# M113C.net
KiCad netlist of a schematic drawn in EAGLE
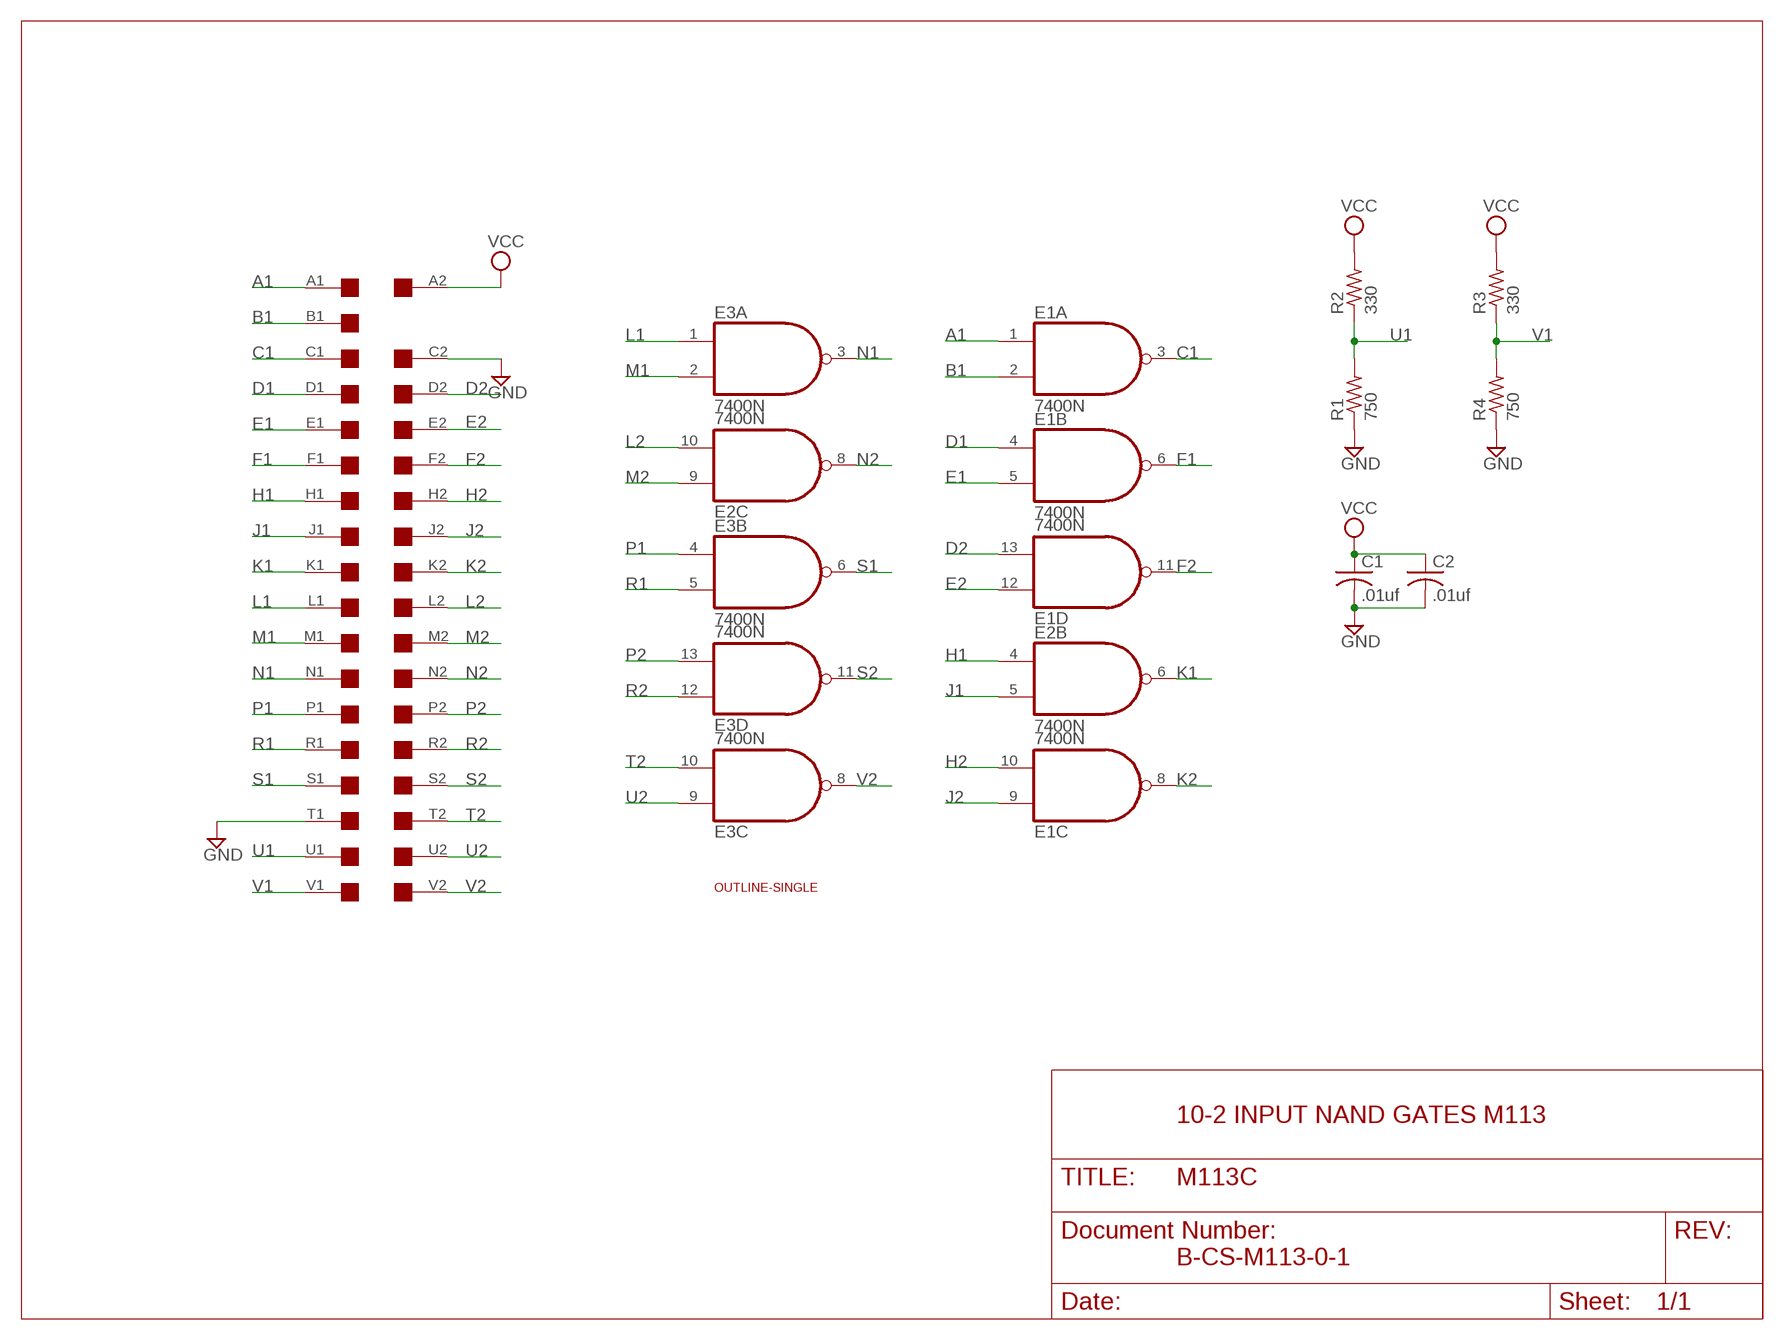
[diagram p0: schematic, sheet 1]

(export (version "E")
  (design (tool "Eeschema 10.0.6"))
  (components
    (comp (ref "C1")
      (value ".01uf")
      (footprint "eagle-import:C050-025X075")
      (libsource (lib "eagle-import") (part "C-US050-025X075"))
    )
    (comp (ref "C2")
      (value ".01uf")
      (footprint "eagle-import:C050-025X075")
      (libsource (lib "eagle-import") (part "C-US050-025X075"))
    )
    (comp (ref "E1")
      (value "7400N")
      (footprint "eagle-import:DIL14")
      (libsource (lib "eagle-import") (part "7400N"))
    )
    (comp (ref "E2")
      (value "7400N")
      (footprint "eagle-import:DIL14")
      (libsource (lib "eagle-import") (part "7400N"))
    )
    (comp (ref "E3")
      (value "7400N")
      (footprint "eagle-import:DIL14")
      (libsource (lib "eagle-import") (part "7400N"))
    )
    (comp (ref "R1")
      (value "750")
      (footprint "eagle-import:0207_10")
      (libsource (lib "eagle-import") (part "R-US_0207/10"))
    )
    (comp (ref "R2")
      (value "330")
      (footprint "eagle-import:0207_10")
      (libsource (lib "eagle-import") (part "R-US_0207/10"))
    )
    (comp (ref "R3")
      (value "330")
      (footprint "eagle-import:0207_10")
      (libsource (lib "eagle-import") (part "R-US_0207/10"))
    )
    (comp (ref "R4")
      (value "750")
      (footprint "eagle-import:0207_10")
      (libsource (lib "eagle-import") (part "R-US_0207/10"))
    )
    (comp (ref "U$1")
      (value "SINGLE")
      (footprint "eagle-import:EDGE-CON2")
      (libsource (lib "eagle-import") (part "SINGLE"))
    )
    (comp (ref "U$2")
      (value "OUTLINE-SINGLE")
      (footprint "eagle-import:SINGLE")
      (libsource (lib "eagle-import") (part "OUTLINE-SINGLE"))
    )
  )
  (nets
    (net (code "1") (name "/A1") (class "Default")
      (node (ref "E1") (pin "1") (pinfunction "I0_1") (pintype "input"))
      (node (ref "U$1") (pin "A1") (pinfunction "1_A1") (pintype "bidirectional"))
    )
    (net (code "2") (name "/B1") (class "Default")
      (node (ref "E1") (pin "2") (pinfunction "I1_2") (pintype "input"))
      (node (ref "U$1") (pin "B1") (pinfunction "1_B1") (pintype "bidirectional"))
    )
    (net (code "3") (name "/C1") (class "Default")
      (node (ref "E1") (pin "3") (pinfunction "O_3") (pintype "output"))
      (node (ref "U$1") (pin "C1") (pinfunction "1_C1") (pintype "bidirectional"))
    )
    (net (code "4") (name "/D1") (class "Default")
      (node (ref "E1") (pin "4") (pinfunction "I0_4") (pintype "input"))
      (node (ref "U$1") (pin "D1") (pinfunction "1_D1") (pintype "bidirectional"))
    )
    (net (code "5") (name "/D2") (class "Default")
      (node (ref "E1") (pin "13") (pinfunction "I1_13") (pintype "input"))
      (node (ref "U$1") (pin "D2") (pinfunction "1_D2") (pintype "bidirectional"))
    )
    (net (code "6") (name "/E1") (class "Default")
      (node (ref "E1") (pin "5") (pinfunction "I1_5") (pintype "input"))
      (node (ref "U$1") (pin "E1") (pinfunction "1_E1") (pintype "bidirectional"))
    )
    (net (code "7") (name "/E2") (class "Default")
      (node (ref "E1") (pin "12") (pinfunction "I0_12") (pintype "input"))
      (node (ref "U$1") (pin "E2") (pinfunction "1_E2") (pintype "bidirectional"))
    )
    (net (code "8") (name "/F1") (class "Default")
      (node (ref "E1") (pin "6") (pinfunction "O_6") (pintype "output"))
      (node (ref "U$1") (pin "F1") (pinfunction "1_F1") (pintype "bidirectional"))
    )
    (net (code "9") (name "/F2") (class "Default")
      (node (ref "E1") (pin "11") (pinfunction "O_11") (pintype "output"))
      (node (ref "U$1") (pin "F2") (pinfunction "1_F2") (pintype "bidirectional"))
    )
    (net (code "10") (name "/H1") (class "Default")
      (node (ref "E2") (pin "4") (pinfunction "I0_4") (pintype "input"))
      (node (ref "U$1") (pin "H1") (pinfunction "1_H1") (pintype "bidirectional"))
    )
    (net (code "11") (name "/H2") (class "Default")
      (node (ref "E1") (pin "10") (pinfunction "I1_10") (pintype "input"))
      (node (ref "U$1") (pin "H2") (pinfunction "1_H2") (pintype "bidirectional"))
    )
    (net (code "12") (name "/J1") (class "Default")
      (node (ref "E2") (pin "5") (pinfunction "I1_5") (pintype "input"))
      (node (ref "U$1") (pin "J1") (pinfunction "1_J1") (pintype "bidirectional"))
    )
    (net (code "13") (name "/J2") (class "Default")
      (node (ref "E1") (pin "9") (pinfunction "I0_9") (pintype "input"))
      (node (ref "U$1") (pin "J2") (pinfunction "1_J2") (pintype "bidirectional"))
    )
    (net (code "14") (name "/K1") (class "Default")
      (node (ref "E2") (pin "6") (pinfunction "O_6") (pintype "output"))
      (node (ref "U$1") (pin "K1") (pinfunction "1_K1") (pintype "bidirectional"))
    )
    (net (code "15") (name "/K2") (class "Default")
      (node (ref "E1") (pin "8") (pinfunction "O_8") (pintype "output"))
      (node (ref "U$1") (pin "K2") (pinfunction "1_K2") (pintype "bidirectional"))
    )
    (net (code "16") (name "/L1") (class "Default")
      (node (ref "E3") (pin "1") (pinfunction "I0_1") (pintype "input"))
      (node (ref "U$1") (pin "L1") (pinfunction "1_L1") (pintype "bidirectional"))
    )
    (net (code "17") (name "/L2") (class "Default")
      (node (ref "E2") (pin "10") (pinfunction "I1_10") (pintype "input"))
      (node (ref "U$1") (pin "L2") (pinfunction "1_L2") (pintype "bidirectional"))
    )
    (net (code "18") (name "/M1") (class "Default")
      (node (ref "E3") (pin "2") (pinfunction "I1_2") (pintype "input"))
      (node (ref "U$1") (pin "M1") (pinfunction "1_M1") (pintype "bidirectional"))
    )
    (net (code "19") (name "/M2") (class "Default")
      (node (ref "E2") (pin "9") (pinfunction "I0_9") (pintype "input"))
      (node (ref "U$1") (pin "M2") (pinfunction "1_M2") (pintype "bidirectional"))
    )
    (net (code "20") (name "/N1") (class "Default")
      (node (ref "E3") (pin "3") (pinfunction "O_3") (pintype "output"))
      (node (ref "U$1") (pin "N1") (pinfunction "1_N1") (pintype "bidirectional"))
    )
    (net (code "21") (name "/N2") (class "Default")
      (node (ref "E2") (pin "8") (pinfunction "O_8") (pintype "output"))
      (node (ref "U$1") (pin "N2") (pinfunction "1_N2") (pintype "bidirectional"))
    )
    (net (code "22") (name "/P1") (class "Default")
      (node (ref "E3") (pin "4") (pinfunction "I0_4") (pintype "input"))
      (node (ref "U$1") (pin "P1") (pinfunction "1_P1") (pintype "bidirectional"))
    )
    (net (code "23") (name "/P2") (class "Default")
      (node (ref "E3") (pin "13") (pinfunction "I1_13") (pintype "input"))
      (node (ref "U$1") (pin "P2") (pinfunction "1_P2") (pintype "bidirectional"))
    )
    (net (code "24") (name "/R1") (class "Default")
      (node (ref "E3") (pin "5") (pinfunction "I1_5") (pintype "input"))
      (node (ref "U$1") (pin "R1") (pinfunction "1_R1") (pintype "bidirectional"))
    )
    (net (code "25") (name "/R2") (class "Default")
      (node (ref "E3") (pin "12") (pinfunction "I0_12") (pintype "input"))
      (node (ref "U$1") (pin "R2") (pinfunction "1_R2") (pintype "bidirectional"))
    )
    (net (code "26") (name "/S1") (class "Default")
      (node (ref "E3") (pin "6") (pinfunction "O_6") (pintype "output"))
      (node (ref "U$1") (pin "S1") (pinfunction "1_S1") (pintype "bidirectional"))
    )
    (net (code "27") (name "/S2") (class "Default")
      (node (ref "E3") (pin "11") (pinfunction "O_11") (pintype "output"))
      (node (ref "U$1") (pin "S2") (pinfunction "1_S2") (pintype "bidirectional"))
    )
    (net (code "28") (name "/T2") (class "Default")
      (node (ref "E3") (pin "10") (pinfunction "I1_10") (pintype "input"))
      (node (ref "U$1") (pin "T2") (pinfunction "1_T2") (pintype "bidirectional"))
    )
    (net (code "29") (name "/U1") (class "Default")
      (node (ref "R1") (pin "2") (pinfunction "2_2") (pintype "passive"))
      (node (ref "R2") (pin "1") (pinfunction "1_1") (pintype "passive"))
      (node (ref "U$1") (pin "U1") (pinfunction "1_U1") (pintype "bidirectional"))
    )
    (net (code "30") (name "/U2") (class "Default")
      (node (ref "E3") (pin "9") (pinfunction "I0_9") (pintype "input"))
      (node (ref "U$1") (pin "U2") (pinfunction "1_U2") (pintype "bidirectional"))
    )
    (net (code "31") (name "/V1") (class "Default")
      (node (ref "R3") (pin "1") (pinfunction "1_1") (pintype "passive"))
      (node (ref "R4") (pin "2") (pinfunction "2_2") (pintype "passive"))
      (node (ref "U$1") (pin "V1") (pinfunction "1_V1") (pintype "bidirectional"))
    )
    (net (code "32") (name "/V2") (class "Default")
      (node (ref "E3") (pin "8") (pinfunction "O_8") (pintype "output"))
      (node (ref "U$1") (pin "V2") (pinfunction "1_V2") (pintype "bidirectional"))
    )
    (net (code "33") (name "GND") (class "Default")
      (node (ref "C1") (pin "2") (pinfunction "2_2") (pintype "passive"))
      (node (ref "C2") (pin "2") (pinfunction "2_2") (pintype "passive"))
      (node (ref "R1") (pin "1") (pinfunction "1_1") (pintype "passive"))
      (node (ref "R4") (pin "1") (pinfunction "1_1") (pintype "passive"))
      (node (ref "U$1") (pin "C2") (pinfunction "1_C2") (pintype "bidirectional"))
      (node (ref "U$1") (pin "T1") (pinfunction "1_T1") (pintype "bidirectional"))
    )
    (net (code "34") (name "VCC") (class "Default")
      (node (ref "C1") (pin "1") (pinfunction "1_1") (pintype "passive"))
      (node (ref "C2") (pin "1") (pinfunction "1_1") (pintype "passive"))
      (node (ref "R2") (pin "2") (pinfunction "2_2") (pintype "passive"))
      (node (ref "R3") (pin "2") (pinfunction "2_2") (pintype "passive"))
      (node (ref "U$1") (pin "A2") (pinfunction "1_A2") (pintype "bidirectional"))
    )
  )
)
